# picr22RobodendronMainboard.net
KiCad netlist of a schematic drawn in Altium Designer
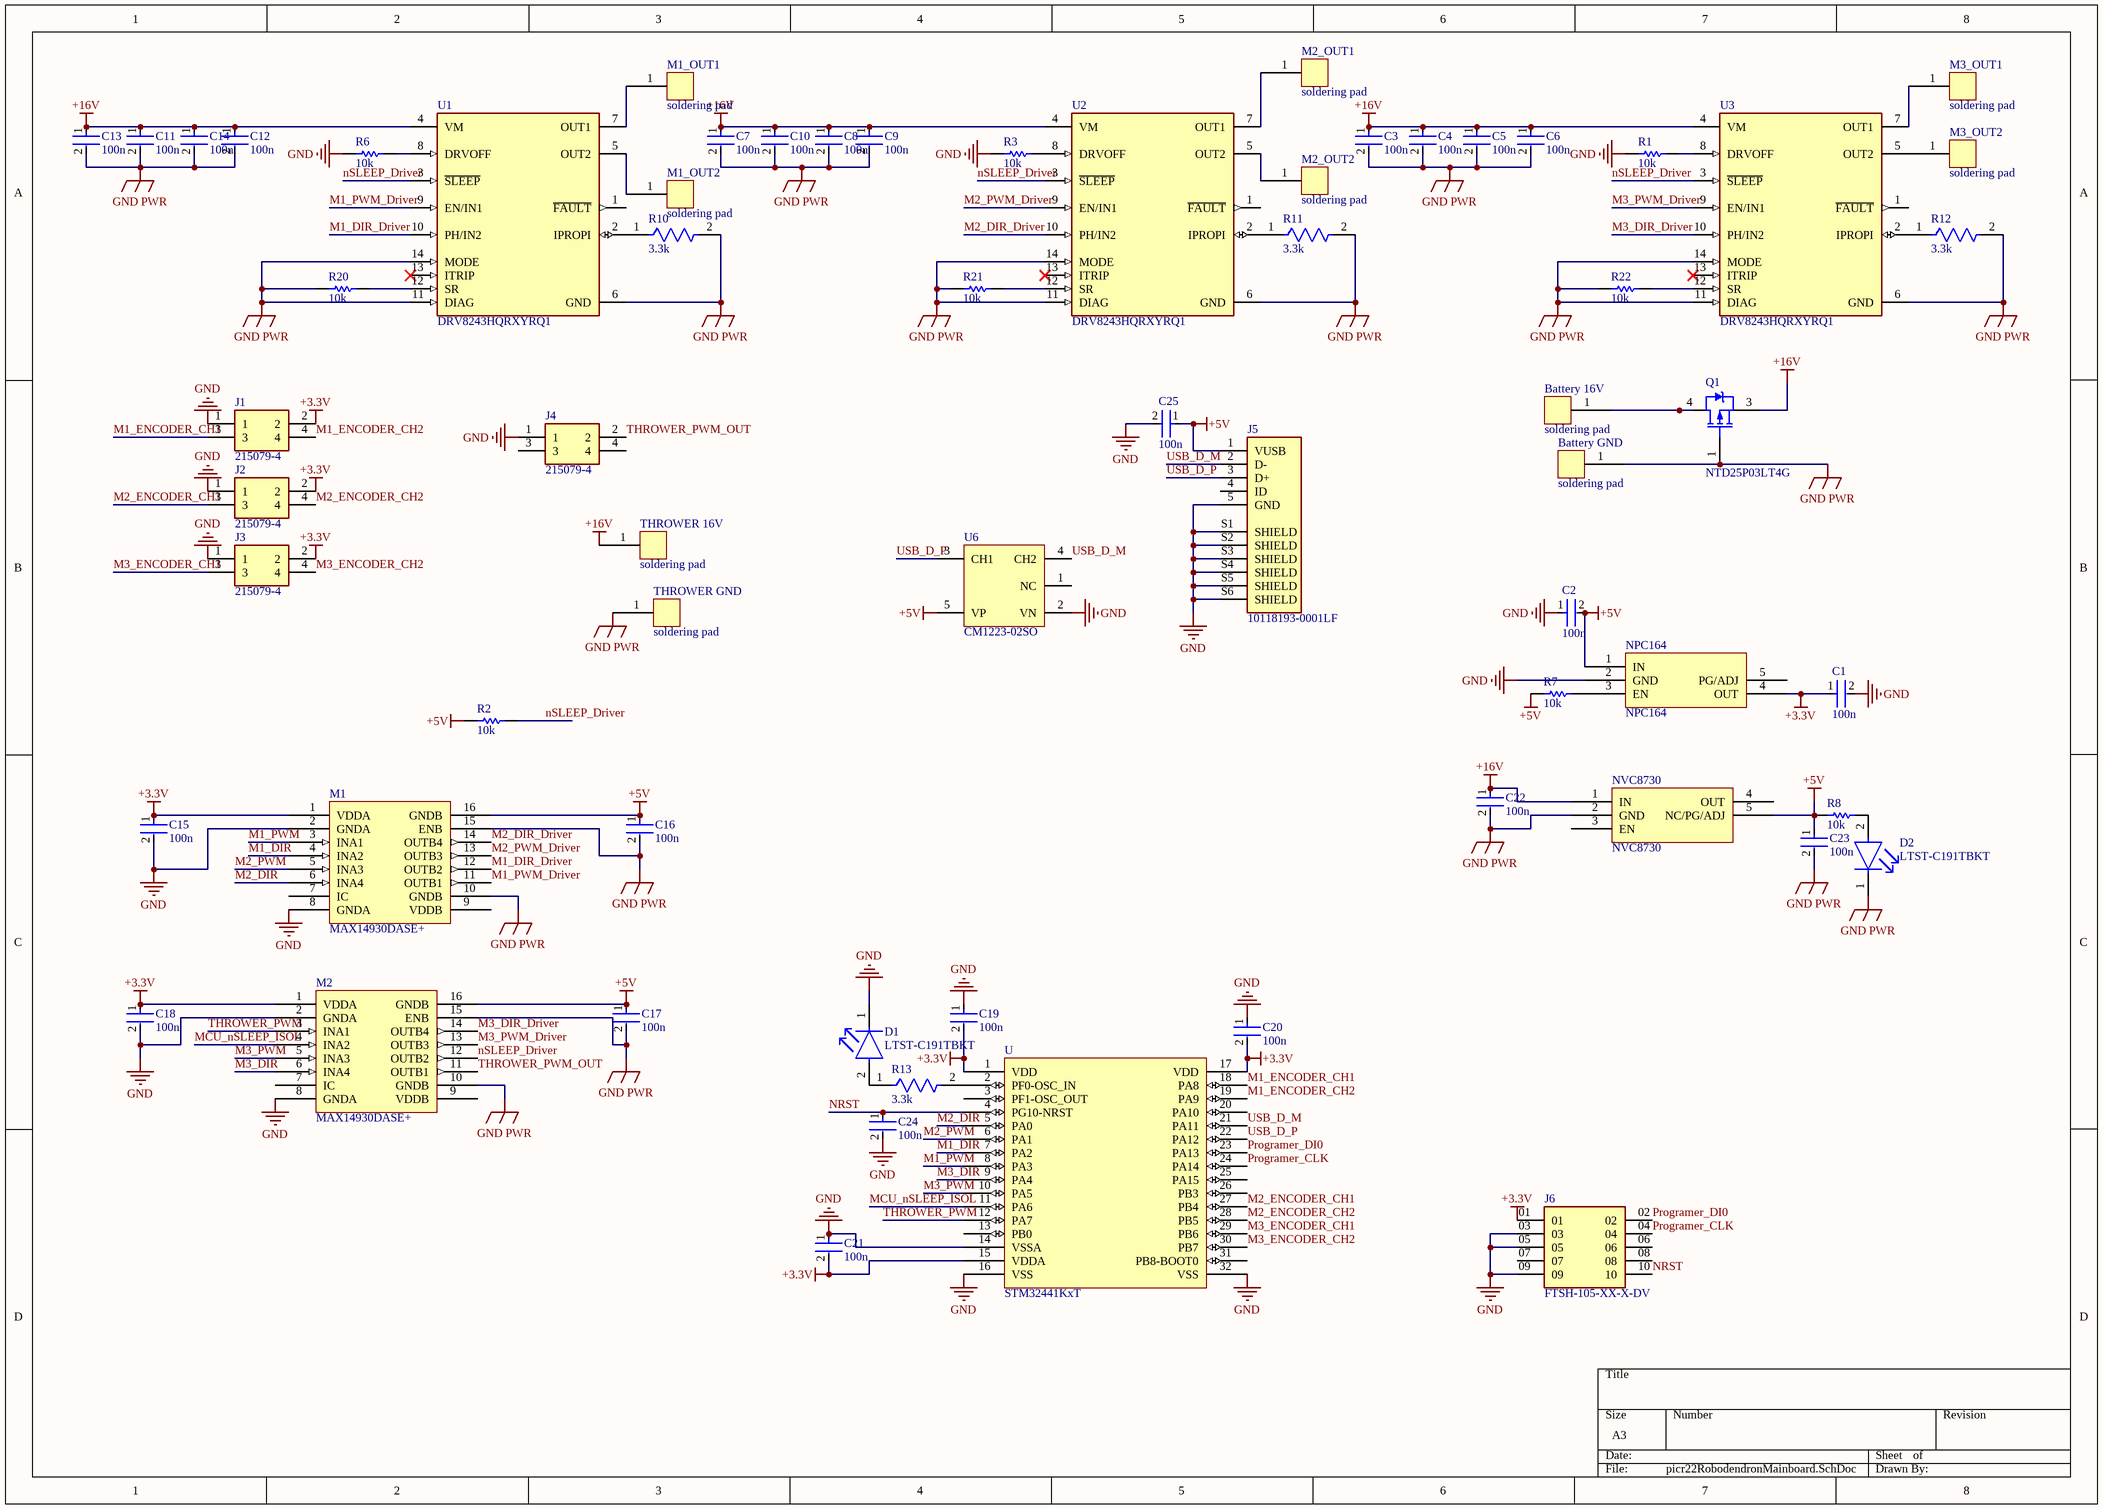
[diagram p0: picr22RobodendronMainboard.SchDoc]

(export (version "E")
  (design (tool "Eeschema 10.0.6"))
  (components
    (comp (ref "Battery 16V")
      (value "soldering pad")
      (footprint "PCBComponent_1")
      (libsource (lib "") (part "soldering pad_1"))
    )
    (comp (ref "Battery GND")
      (value "soldering pad")
      (footprint "PCBComponent_1")
      (libsource (lib "") (part "soldering pad_1"))
    )
    (comp (ref "C1")
      (value "100n")
      (footprint "FP-CGA3E-0_3-0_1-IPC_A")
      (description "Cap Ceramic 100nF 50V X7R 10% Pad SMD 0603 +125°C Automotive T/R")
      (fields (field (name "TOLERANCE") "10%") (field (name "VOLTAGE") "50V"))
      (libsource (lib "Altium Content Vault") (part "b4654b650e69147ec39a6b967a45e02"))
    )
    (comp (ref "C2")
      (value "100n")
      (footprint "FP-CGA3E-0_3-0_1-IPC_A")
      (description "Cap Ceramic 100nF 50V X7R 10% Pad SMD 0603 +125°C Automotive T/R")
      (fields (field (name "TOLERANCE") "10%") (field (name "VOLTAGE") "50V"))
      (libsource (lib "Altium Content Vault") (part "b4654b650e69147ec39a6b967a45e02"))
    )
    (comp (ref "C3")
      (value "100n")
      (footprint "FP-CGA3E-0_3-0_1-IPC_A")
      (description "Cap Ceramic 100nF 50V X7R 10% Pad SMD 0603 +125°C Automotive T/R")
      (fields (field (name "TOLERANCE") "10%") (field (name "VOLTAGE") "50V"))
      (libsource (lib "Altium Content Vault") (part "b4654b650e69147ec39a6b967a45e02"))
    )
    (comp (ref "C4")
      (value "100n")
      (footprint "FP-CGA3E-0_3-0_1-IPC_A")
      (description "Cap Ceramic 100nF 50V X7R 10% Pad SMD 0603 +125°C Automotive T/R")
      (fields (field (name "TOLERANCE") "10%") (field (name "VOLTAGE") "50V"))
      (libsource (lib "Altium Content Vault") (part "b4654b650e69147ec39a6b967a45e02"))
    )
    (comp (ref "C5")
      (value "100n")
      (footprint "FP-CGA3E-0_3-0_1-IPC_A")
      (description "Cap Ceramic 100nF 50V X7R 10% Pad SMD 0603 +125°C Automotive T/R")
      (fields (field (name "TOLERANCE") "10%") (field (name "VOLTAGE") "50V"))
      (libsource (lib "Altium Content Vault") (part "b4654b650e69147ec39a6b967a45e02"))
    )
    (comp (ref "C6")
      (value "100n")
      (footprint "FP-CGA3E-0_3-0_1-IPC_A")
      (description "Cap Ceramic 100nF 50V X7R 10% Pad SMD 0603 +125°C Automotive T/R")
      (fields (field (name "TOLERANCE") "10%") (field (name "VOLTAGE") "50V"))
      (libsource (lib "Altium Content Vault") (part "b4654b650e69147ec39a6b967a45e02"))
    )
    (comp (ref "C7")
      (value "100n")
      (footprint "FP-CGA3E-0_3-0_1-IPC_A")
      (description "Cap Ceramic 100nF 50V X7R 10% Pad SMD 0603 +125°C Automotive T/R")
      (fields (field (name "TOLERANCE") "10%") (field (name "VOLTAGE") "50V"))
      (libsource (lib "Altium Content Vault") (part "b4654b650e69147ec39a6b967a45e02"))
    )
    (comp (ref "C8")
      (value "100n")
      (footprint "FP-CGA3E-0_3-0_1-IPC_A")
      (description "Cap Ceramic 100nF 50V X7R 10% Pad SMD 0603 +125°C Automotive T/R")
      (fields (field (name "TOLERANCE") "10%") (field (name "VOLTAGE") "50V"))
      (libsource (lib "Altium Content Vault") (part "b4654b650e69147ec39a6b967a45e02"))
    )
    (comp (ref "C9")
      (value "100n")
      (footprint "FP-CGA3E-0_3-0_1-IPC_A")
      (description "Cap Ceramic 100nF 50V X7R 10% Pad SMD 0603 +125°C Automotive T/R")
      (fields (field (name "TOLERANCE") "10%") (field (name "VOLTAGE") "50V"))
      (libsource (lib "Altium Content Vault") (part "b4654b650e69147ec39a6b967a45e02"))
    )
    (comp (ref "C10")
      (value "100n")
      (footprint "FP-CGA3E-0_3-0_1-IPC_A")
      (description "Cap Ceramic 100nF 50V X7R 10% Pad SMD 0603 +125°C Automotive T/R")
      (fields (field (name "TOLERANCE") "10%") (field (name "VOLTAGE") "50V"))
      (libsource (lib "Altium Content Vault") (part "b4654b650e69147ec39a6b967a45e02"))
    )
    (comp (ref "C11")
      (value "100n")
      (footprint "FP-CGA3E-0_3-0_1-IPC_A")
      (description "Cap Ceramic 100nF 50V X7R 10% Pad SMD 0603 +125°C Automotive T/R")
      (fields (field (name "TOLERANCE") "10%") (field (name "VOLTAGE") "50V"))
      (libsource (lib "Altium Content Vault") (part "b4654b650e69147ec39a6b967a45e02"))
    )
    (comp (ref "C12")
      (value "100n")
      (footprint "FP-CGA3E-0_3-0_1-IPC_A")
      (description "Cap Ceramic 100nF 50V X7R 10% Pad SMD 0603 +125°C Automotive T/R")
      (fields (field (name "TOLERANCE") "10%") (field (name "VOLTAGE") "50V"))
      (libsource (lib "Altium Content Vault") (part "b4654b650e69147ec39a6b967a45e02"))
    )
    (comp (ref "C13")
      (value "100n")
      (footprint "FP-CGA3E-0_3-0_1-IPC_A")
      (description "Cap Ceramic 100nF 50V X7R 10% Pad SMD 0603 +125°C Automotive T/R")
      (fields (field (name "TOLERANCE") "10%") (field (name "VOLTAGE") "50V"))
      (libsource (lib "Altium Content Vault") (part "b4654b650e69147ec39a6b967a45e02"))
    )
    (comp (ref "C14")
      (value "100n")
      (footprint "FP-CGA3E-0_3-0_1-IPC_A")
      (description "Cap Ceramic 100nF 50V X7R 10% Pad SMD 0603 +125°C Automotive T/R")
      (fields (field (name "TOLERANCE") "10%") (field (name "VOLTAGE") "50V"))
      (libsource (lib "Altium Content Vault") (part "b4654b650e69147ec39a6b967a45e02"))
    )
    (comp (ref "C15")
      (value "100n")
      (footprint "FP-CGA3E-0_3-0_1-IPC_A")
      (description "Cap Ceramic 100nF 50V X7R 10% Pad SMD 0603 +125°C Automotive T/R")
      (fields (field (name "TOLERANCE") "10%") (field (name "VOLTAGE") "50V"))
      (libsource (lib "Altium Content Vault") (part "b4654b650e69147ec39a6b967a45e02"))
    )
    (comp (ref "C16")
      (value "100n")
      (footprint "FP-CGA3E-0_3-0_1-IPC_A")
      (description "Cap Ceramic 100nF 50V X7R 10% Pad SMD 0603 +125°C Automotive T/R")
      (fields (field (name "TOLERANCE") "10%") (field (name "VOLTAGE") "50V"))
      (libsource (lib "Altium Content Vault") (part "b4654b650e69147ec39a6b967a45e02"))
    )
    (comp (ref "C17")
      (value "100n")
      (footprint "FP-CGA3E-0_3-0_1-IPC_A")
      (description "Cap Ceramic 100nF 50V X7R 10% Pad SMD 0603 +125°C Automotive T/R")
      (fields (field (name "TOLERANCE") "10%") (field (name "VOLTAGE") "50V"))
      (libsource (lib "Altium Content Vault") (part "b4654b650e69147ec39a6b967a45e02"))
    )
    (comp (ref "C18")
      (value "100n")
      (footprint "FP-CGA3E-0_3-0_1-IPC_A")
      (description "Cap Ceramic 100nF 50V X7R 10% Pad SMD 0603 +125°C Automotive T/R")
      (fields (field (name "TOLERANCE") "10%") (field (name "VOLTAGE") "50V"))
      (libsource (lib "Altium Content Vault") (part "b4654b650e69147ec39a6b967a45e02"))
    )
    (comp (ref "C19")
      (value "100n")
      (footprint "FP-CGA3E-0_3-0_1-IPC_A")
      (description "Cap Ceramic 100nF 50V X7R 10% Pad SMD 0603 +125°C Automotive T/R")
      (fields (field (name "TOLERANCE") "10%") (field (name "VOLTAGE") "50V"))
      (libsource (lib "Altium Content Vault") (part "b4654b650e69147ec39a6b967a45e02"))
    )
    (comp (ref "C20")
      (value "100n")
      (footprint "FP-CGA3E-0_3-0_1-IPC_A")
      (description "Cap Ceramic 100nF 50V X7R 10% Pad SMD 0603 +125°C Automotive T/R")
      (fields (field (name "TOLERANCE") "10%") (field (name "VOLTAGE") "50V"))
      (libsource (lib "Altium Content Vault") (part "b4654b650e69147ec39a6b967a45e02"))
    )
    (comp (ref "C21")
      (value "100n")
      (footprint "FP-CGA3E-0_3-0_1-IPC_A")
      (description "Cap Ceramic 100nF 50V X7R 10% Pad SMD 0603 +125°C Automotive T/R")
      (fields (field (name "TOLERANCE") "10%") (field (name "VOLTAGE") "50V"))
      (libsource (lib "Altium Content Vault") (part "b4654b650e69147ec39a6b967a45e02"))
    )
    (comp (ref "C22")
      (value "100n")
      (footprint "FP-CGA3E-0_3-0_1-IPC_A")
      (description "Cap Ceramic 100nF 50V X7R 10% Pad SMD 0603 +125°C Automotive T/R")
      (fields (field (name "TOLERANCE") "10%") (field (name "VOLTAGE") "50V"))
      (libsource (lib "Altium Content Vault") (part "b4654b650e69147ec39a6b967a45e02"))
    )
    (comp (ref "C23")
      (value "100n")
      (footprint "FP-CGA3E-0_3-0_1-IPC_A")
      (description "Cap Ceramic 100nF 50V X7R 10% Pad SMD 0603 +125°C Automotive T/R")
      (fields (field (name "TOLERANCE") "10%") (field (name "VOLTAGE") "50V"))
      (libsource (lib "Altium Content Vault") (part "b4654b650e69147ec39a6b967a45e02"))
    )
    (comp (ref "C24")
      (value "100n")
      (footprint "FP-CGA3E-0_3-0_1-IPC_A")
      (description "Cap Ceramic 100nF 50V X7R 10% Pad SMD 0603 +125°C Automotive T/R")
      (fields (field (name "TOLERANCE") "10%") (field (name "VOLTAGE") "50V"))
      (libsource (lib "Altium Content Vault") (part "b4654b650e69147ec39a6b967a45e02"))
    )
    (comp (ref "C25")
      (value "100n")
      (footprint "FP-CGA3E-0_3-0_1-IPC_A")
      (description "Cap Ceramic 100nF 50V X7R 10% Pad SMD 0603 +125°C Automotive T/R")
      (fields (field (name "TOLERANCE") "10%") (field (name "VOLTAGE") "50V"))
      (libsource (lib "Altium Content Vault") (part "b4654b650e69147ec39a6b967a45e02"))
    )
    (comp (ref "D1")
      (value "LTST-C191TBKT")
      (footprint "FP-LTST-C191TBKT-MFG")
      (description "LED BLUE CLEAR CHIP SMD")
      (libsource (lib "Altium Content Vault") (part "8706943c75ba83719d021d2fdc84c58"))
    )
    (comp (ref "D2")
      (value "LTST-C191TBKT")
      (footprint "FP-LTST-C191TBKT-MFG")
      (description "LED BLUE CLEAR CHIP SMD")
      (libsource (lib "Altium Content Vault") (part "8706943c75ba83719d021d2fdc84c58"))
    )
    (comp (ref "J1")
      (value "215079-4")
      (footprint "TE_215079-4")
      (description "4 Position Receptacle Connector Through Hole")
      (fields (field (name "MF") "TE Connectivity"))
      (libsource (lib "215079-4") (part "215079-4"))
    )
    (comp (ref "J2")
      (value "215079-4")
      (footprint "TE_215079-4")
      (description "4 Position Receptacle Connector Through Hole")
      (fields (field (name "MF") "TE Connectivity"))
      (libsource (lib "215079-4") (part "215079-4"))
    )
    (comp (ref "J3")
      (value "215079-4")
      (footprint "TE_215079-4")
      (description "4 Position Receptacle Connector Through Hole")
      (fields (field (name "MF") "TE Connectivity"))
      (libsource (lib "215079-4") (part "215079-4"))
    )
    (comp (ref "J4")
      (value "215079-4")
      (footprint "TE_215079-4")
      (description "4 Position Receptacle Connector Through Hole")
      (fields (field (name "MF") "TE Connectivity"))
      (libsource (lib "215079-4") (part "215079-4"))
    )
    (comp (ref "J5")
      (value "10118193-0001LF")
      (footprint "FCI_10118193-0001LF")
      (description "USB - micro B USB 2.0 Receptacle Connector 5 Position Surface Mount, Right Angle; Through Hole")
      (fields (field (name "MF") "Amphenol ICC"))
      (libsource (lib "10118193-0001LF") (part "10118193-0001LF"))
    )
    (comp (ref "J6")
      (value "FTSH-105-XX-X-DV")
      (footprint "SAMTEC_FTSH-105-XX-X-DV")
      (description "Connector Header Surface Mount 10 position 0.050\" (1.27mm)")
      (libsource (lib "FTSH-105-XX-X-DV") (part "FTSH-105-XX-X-DV"))
    )
    (comp (ref "M1")
      (value "MAX14930DASE+")
      (footprint "SOIC127P600X175-16N")
      (libsource (lib "picr22RobodendronMainboard") (part "MAX14930DASE+"))
    )
    (comp (ref "M1_OUT1")
      (value "soldering pad")
      (footprint "PCBComponent_1")
      (libsource (lib "picr22RobodendronMainboard") (part "soldering pad"))
    )
    (comp (ref "M1_OUT2")
      (value "soldering pad")
      (footprint "PCBComponent_1")
      (libsource (lib "picr22RobodendronMainboard") (part "soldering pad"))
    )
    (comp (ref "M2")
      (value "MAX14930DASE+")
      (footprint "SOIC127P600X175-16N")
      (libsource (lib "picr22RobodendronMainboard") (part "MAX14930DASE+"))
    )
    (comp (ref "M2_OUT1")
      (value "soldering pad")
      (footprint "PCBComponent_1")
      (libsource (lib "picr22RobodendronMainboard") (part "soldering pad"))
    )
    (comp (ref "M2_OUT2")
      (value "soldering pad")
      (footprint "PCBComponent_1")
      (libsource (lib "picr22RobodendronMainboard") (part "soldering pad"))
    )
    (comp (ref "M3_OUT1")
      (value "soldering pad")
      (footprint "PCBComponent_1")
      (libsource (lib "picr22RobodendronMainboard") (part "soldering pad"))
    )
    (comp (ref "M3_OUT2")
      (value "soldering pad")
      (footprint "PCBComponent_1")
      (libsource (lib "picr22RobodendronMainboard") (part "soldering pad"))
    )
    (comp (ref "NPC164")
      (value "NPC164")
      (footprint "TSOP95P280X110-5N")
      (libsource (lib "picr22RobodendronMainboard") (part "NPC164"))
    )
    (comp (ref "NVC8730")
      (value "NVC8730")
      (footprint "TSOP95P280X110-6N")
      (libsource (lib "picr22RobodendronMainboard") (part "NVC8730"))
    )
    (comp (ref "Q1")
      (value "NTD25P03LT4G")
      (footprint "ONSC-DPAK-3-369C-01_V")
      (description "Power MOSFET, -25 A, -30 V, Logic Level P-Channel, 3-Pin DPAK, Pb-Free, Tape and Reel")
      (fields (field (name "MANUFACTURER") "On Semiconductor"))
      (libsource (lib "Altium Content Vault") (part "ONSC-PMOS-G1S3D4-3_B"))
    )
    (comp (ref "R1")
      (value "10k")
      (footprint "RESC1609X50X30NL8T20")
      (description "Chip Resistor, 10 KOhm, +/- 1%, 100 mW, -55 to 155 degC, 0603 (1608 Metric), RoHS, Tape and Reel")
      (fields (field (name "MANUFACTURER") "Vishay Semiconductor"))
      (libsource (lib "Altium Content Vault") (part "RES-2"))
    )
    (comp (ref "R2")
      (value "10k")
      (footprint "RESC1609X50X30NL8T20")
      (description "Chip Resistor, 10 KOhm, +/- 1%, 100 mW, -55 to 155 degC, 0603 (1608 Metric), RoHS, Tape and Reel")
      (fields (field (name "MANUFACTURER") "Vishay Semiconductor"))
      (libsource (lib "Altium Content Vault") (part "RES-2"))
    )
    (comp (ref "R3")
      (value "10k")
      (footprint "RESC1609X50X30NL8T20")
      (description "Chip Resistor, 10 KOhm, +/- 1%, 100 mW, -55 to 155 degC, 0603 (1608 Metric), RoHS, Tape and Reel")
      (fields (field (name "MANUFACTURER") "Vishay Semiconductor"))
      (libsource (lib "Altium Content Vault") (part "RES-2"))
    )
    (comp (ref "R6")
      (value "10k")
      (footprint "RESC1609X50X30NL8T20")
      (description "Chip Resistor, 10 KOhm, +/- 1%, 100 mW, -55 to 155 degC, 0603 (1608 Metric), RoHS, Tape and Reel")
      (fields (field (name "MANUFACTURER") "Vishay Semiconductor"))
      (libsource (lib "Altium Content Vault") (part "RES-2"))
    )
    (comp (ref "R7")
      (value "10k")
      (footprint "RESC1609X50X30NL8T20")
      (description "Chip Resistor, 10 KOhm, +/- 1%, 100 mW, -55 to 155 degC, 0603 (1608 Metric), RoHS, Tape and Reel")
      (fields (field (name "MANUFACTURER") "Vishay Semiconductor"))
      (libsource (lib "Altium Content Vault") (part "RES-2"))
    )
    (comp (ref "R8")
      (value "10k")
      (footprint "RESC1609X50X30NL8T20")
      (description "Chip Resistor, 10 KOhm, +/- 1%, 100 mW, -55 to 155 degC, 0603 (1608 Metric), RoHS, Tape and Reel")
      (fields (field (name "MANUFACTURER") "Vishay Semiconductor"))
      (libsource (lib "Altium Content Vault") (part "RES-2"))
    )
    (comp (ref "R10")
      (value "3.3k")
      (footprint "FP-ERA3A-IPC_B")
      (description "RES SMD 3.3K OHM 0.1% 1/10W 0603")
      (fields (field (name "TOLERANCE") "0.1%"))
      (libsource (lib "Altium Content Vault") (part "1029c3af85768c4190bb7ad29bc67b5"))
    )
    (comp (ref "R11")
      (value "3.3k")
      (footprint "FP-ERA3A-IPC_B")
      (description "RES SMD 3.3K OHM 0.1% 1/10W 0603")
      (fields (field (name "TOLERANCE") "0.1%"))
      (libsource (lib "Altium Content Vault") (part "1029c3af85768c4190bb7ad29bc67b5"))
    )
    (comp (ref "R12")
      (value "3.3k")
      (footprint "FP-ERA3A-IPC_B")
      (description "RES SMD 3.3K OHM 0.1% 1/10W 0603")
      (fields (field (name "TOLERANCE") "0.1%"))
      (libsource (lib "Altium Content Vault") (part "1029c3af85768c4190bb7ad29bc67b5"))
    )
    (comp (ref "R13")
      (value "3.3k")
      (footprint "FP-ERA3A-IPC_B")
      (description "RES SMD 3.3K OHM 0.1% 1/10W 0603")
      (fields (field (name "TOLERANCE") "0.1%"))
      (libsource (lib "Altium Content Vault") (part "1029c3af85768c4190bb7ad29bc67b5"))
    )
    (comp (ref "R20")
      (value "10k")
      (footprint "RESC1609X50X30NL8T20")
      (description "Chip Resistor, 10 KOhm, +/- 1%, 100 mW, -55 to 155 degC, 0603 (1608 Metric), RoHS, Tape and Reel")
      (fields (field (name "MANUFACTURER") "Vishay Semiconductor"))
      (libsource (lib "Altium Content Vault") (part "RES-2"))
    )
    (comp (ref "R21")
      (value "10k")
      (footprint "RESC1609X50X30NL8T20")
      (description "Chip Resistor, 10 KOhm, +/- 1%, 100 mW, -55 to 155 degC, 0603 (1608 Metric), RoHS, Tape and Reel")
      (fields (field (name "MANUFACTURER") "Vishay Semiconductor"))
      (libsource (lib "Altium Content Vault") (part "RES-2"))
    )
    (comp (ref "R22")
      (value "10k")
      (footprint "RESC1609X50X30NL8T20")
      (description "Chip Resistor, 10 KOhm, +/- 1%, 100 mW, -55 to 155 degC, 0603 (1608 Metric), RoHS, Tape and Reel")
      (fields (field (name "MANUFACTURER") "Vishay Semiconductor"))
      (libsource (lib "Altium Content Vault") (part "RES-2"))
    )
    (comp (ref "THROWER 16V")
      (value "soldering pad")
      (footprint "PCBComponent_1")
      (libsource (lib "picr22RobodendronMainboard") (part "soldering pad"))
    )
    (comp (ref "THROWER GND")
      (value "soldering pad")
      (footprint "PCBComponent_1")
      (libsource (lib "picr22RobodendronMainboard") (part "soldering pad"))
    )
    (comp (ref "U")
      (value "STM32441KxT")
      (footprint "TQFP80P890X890X160-32N")
      (libsource (lib "picr22RobodendronMainboard") (part "STM32441"))
    )
    (comp (ref "U1")
      (value "DRV8243HQRXYRQ1")
      (footprint "FP-RXY0014A-MFG")
      (libsource (lib "Altium Content Vault") (part "e63e13eb07ecfdbca845f52d5221c39"))
    )
    (comp (ref "U2")
      (value "DRV8243HQRXYRQ1")
      (footprint "FP-RXY0014A-MFG")
      (libsource (lib "Altium Content Vault") (part "e63e13eb07ecfdbca845f52d5221c39"))
    )
    (comp (ref "U3")
      (value "DRV8243HQRXYRQ1")
      (footprint "FP-RXY0014A-MFG")
      (libsource (lib "Altium Content Vault") (part "e63e13eb07ecfdbca845f52d5221c39"))
    )
    (comp (ref "U6")
      (value "CM1223-02SO")
      (footprint "ONSC-SOT23-5-527AH-01_L")
      (fields (field (name "MANUFACTURER") "On Semiconductor"))
      (libsource (lib "Altium Content Vault") (part "ONSC-CM1223-SOT-23-5-527AH-01"))
    )
  )
  (nets
    (net (code "1") (name "+3.3V") (class "Default")
      (node (ref "C1") (pin "1") (pinfunction "1_1") (pintype "passive"))
      (node (ref "C15") (pin "1") (pinfunction "1_1") (pintype "passive"))
      (node (ref "C18") (pin "1") (pinfunction "1_1") (pintype "passive"))
      (node (ref "C19") (pin "2") (pinfunction "2_2") (pintype "passive"))
      (node (ref "C20") (pin "2") (pinfunction "2_2") (pintype "passive"))
      (node (ref "C21") (pin "2") (pinfunction "2_2") (pintype "passive"))
      (node (ref "J1") (pin "2") (pinfunction "2_2") (pintype "passive"))
      (node (ref "J2") (pin "2") (pinfunction "2_2") (pintype "passive"))
      (node (ref "J3") (pin "2") (pinfunction "2_2") (pintype "passive"))
      (node (ref "J6") (pin "01") (pinfunction "01_01") (pintype "passive"))
      (node (ref "M1") (pin "1") (pinfunction "VDDA_1") (pintype "power_in"))
      (node (ref "M2") (pin "1") (pinfunction "VDDA_1") (pintype "power_in"))
      (node (ref "NPC164") (pin "4") (pinfunction "OUT_4") (pintype "power_in"))
      (node (ref "U") (pin "1") (pinfunction "VDD_1") (pintype "power_in"))
      (node (ref "U") (pin "15") (pinfunction "VDDA_15") (pintype "power_in"))
      (node (ref "U") (pin "17") (pinfunction "VDD_17") (pintype "power_in"))
    )
    (net (code "2") (name "+5V") (class "Default")
      (node (ref "C16") (pin "1") (pinfunction "1_1") (pintype "passive"))
      (node (ref "C17") (pin "1") (pinfunction "1_1") (pintype "passive"))
      (node (ref "C2") (pin "2") (pinfunction "2_2") (pintype "passive"))
      (node (ref "C23") (pin "1") (pinfunction "1_1") (pintype "passive"))
      (node (ref "C25") (pin "1") (pinfunction "1_1") (pintype "passive"))
      (node (ref "J5") (pin "1") (pinfunction "VUSB_1") (pintype "passive"))
      (node (ref "M1") (pin "16") (pinfunction "GNDB_16") (pintype "power_in"))
      (node (ref "M2") (pin "16") (pinfunction "GNDB_16") (pintype "power_in"))
      (node (ref "NPC164") (pin "1") (pinfunction "IN_1") (pintype "power_in"))
      (node (ref "NVC8730") (pin "5") (pinfunction "NC/PG/ADJ_5") (pintype "passive"))
      (node (ref "R2") (pin "1") (pinfunction "1_1") (pintype "passive"))
      (node (ref "R7") (pin "1") (pinfunction "1_1") (pintype "passive"))
      (node (ref "R8") (pin "1") (pinfunction "1_1") (pintype "passive"))
      (node (ref "U6") (pin "5") (pinfunction "VP_5") (pintype "power_in"))
    )
    (net (code "3") (name "+16V") (class "Default")
      (node (ref "C10") (pin "1") (pinfunction "1_1") (pintype "passive"))
      (node (ref "C11") (pin "1") (pinfunction "1_1") (pintype "passive"))
      (node (ref "C12") (pin "1") (pinfunction "1_1") (pintype "passive"))
      (node (ref "C13") (pin "1") (pinfunction "1_1") (pintype "passive"))
      (node (ref "C14") (pin "1") (pinfunction "1_1") (pintype "passive"))
      (node (ref "C22") (pin "1") (pinfunction "1_1") (pintype "passive"))
      (node (ref "C3") (pin "1") (pinfunction "1_1") (pintype "passive"))
      (node (ref "C4") (pin "1") (pinfunction "1_1") (pintype "passive"))
      (node (ref "C5") (pin "1") (pinfunction "1_1") (pintype "passive"))
      (node (ref "C6") (pin "1") (pinfunction "1_1") (pintype "passive"))
      (node (ref "C7") (pin "1") (pinfunction "1_1") (pintype "passive"))
      (node (ref "C8") (pin "1") (pinfunction "1_1") (pintype "passive"))
      (node (ref "C9") (pin "1") (pinfunction "1_1") (pintype "passive"))
      (node (ref "NVC8730") (pin "1") (pinfunction "IN_1") (pintype "power_in"))
      (node (ref "Q1") (pin "3") (pinfunction "S_3") (pintype "passive"))
      (node (ref "THROWER 16V") (pin "1") (pintype "power_in"))
      (node (ref "U1") (pin "4") (pinfunction "VM_4") (pintype "power_in"))
      (node (ref "U2") (pin "4") (pinfunction "VM_4") (pintype "power_in"))
      (node (ref "U3") (pin "4") (pinfunction "VM_4") (pintype "power_in"))
    )
    (net (code "4") (name "/M1_DIR") (class "Default")
      (node (ref "M1") (pin "4") (pinfunction "INA2_4") (pintype "input"))
      (node (ref "U") (pin "7") (pinfunction "PA2_7") (pintype "bidirectional"))
    )
    (net (code "5") (name "/M1_DIR_Driver") (class "Default")
      (node (ref "M1") (pin "12") (pinfunction "OUTB2_12") (pintype "output"))
      (node (ref "U1") (pin "10") (pinfunction "PH/IN2_10") (pintype "input"))
    )
    (net (code "6") (name "/M1_ENCODER_CH1") (class "Default")
      (node (ref "J1") (pin "3") (pinfunction "3_3") (pintype "passive"))
      (node (ref "U") (pin "18") (pinfunction "PA8_18") (pintype "bidirectional"))
    )
    (net (code "7") (name "/M1_ENCODER_CH2") (class "Default")
      (node (ref "J1") (pin "4") (pinfunction "4_4") (pintype "passive"))
      (node (ref "U") (pin "19") (pinfunction "PA9_19") (pintype "bidirectional"))
    )
    (net (code "8") (name "/M1_PWM") (class "Default")
      (node (ref "M1") (pin "3") (pinfunction "INA1_3") (pintype "input"))
      (node (ref "U") (pin "8") (pinfunction "PA3_8") (pintype "bidirectional"))
    )
    (net (code "9") (name "/M1_PWM_Driver") (class "Default")
      (node (ref "M1") (pin "11") (pinfunction "OUTB1_11") (pintype "output"))
      (node (ref "U1") (pin "9") (pinfunction "EN/IN1_9") (pintype "input"))
    )
    (net (code "10") (name "/M2_DIR") (class "Default")
      (node (ref "M1") (pin "6") (pinfunction "INA4_6") (pintype "input"))
      (node (ref "U") (pin "5") (pinfunction "PA0_5") (pintype "bidirectional"))
    )
    (net (code "11") (name "/M2_DIR_Driver") (class "Default")
      (node (ref "M1") (pin "14") (pinfunction "OUTB4_14") (pintype "output"))
      (node (ref "U2") (pin "10") (pinfunction "PH/IN2_10") (pintype "input"))
    )
    (net (code "12") (name "/M2_ENCODER_CH1") (class "Default")
      (node (ref "J2") (pin "3") (pinfunction "3_3") (pintype "passive"))
      (node (ref "U") (pin "27") (pinfunction "PB4_27") (pintype "bidirectional"))
    )
    (net (code "13") (name "/M2_ENCODER_CH2") (class "Default")
      (node (ref "J2") (pin "4") (pinfunction "4_4") (pintype "passive"))
      (node (ref "U") (pin "28") (pinfunction "PB5_28") (pintype "bidirectional"))
    )
    (net (code "14") (name "/M2_PWM") (class "Default")
      (node (ref "M1") (pin "5") (pinfunction "INA3_5") (pintype "input"))
      (node (ref "U") (pin "6") (pinfunction "PA1_6") (pintype "bidirectional"))
    )
    (net (code "15") (name "/M2_PWM_Driver") (class "Default")
      (node (ref "M1") (pin "13") (pinfunction "OUTB3_13") (pintype "output"))
      (node (ref "U2") (pin "9") (pinfunction "EN/IN1_9") (pintype "input"))
    )
    (net (code "16") (name "/M3_DIR") (class "Default")
      (node (ref "M2") (pin "6") (pinfunction "INA4_6") (pintype "input"))
      (node (ref "U") (pin "9") (pinfunction "PA4_9") (pintype "bidirectional"))
    )
    (net (code "17") (name "/M3_DIR_Driver") (class "Default")
      (node (ref "M2") (pin "14") (pinfunction "OUTB4_14") (pintype "output"))
      (node (ref "U3") (pin "10") (pinfunction "PH/IN2_10") (pintype "input"))
    )
    (net (code "18") (name "/M3_ENCODER_CH1") (class "Default")
      (node (ref "J3") (pin "3") (pinfunction "3_3") (pintype "passive"))
      (node (ref "U") (pin "29") (pinfunction "PB6_29") (pintype "bidirectional"))
    )
    (net (code "19") (name "/M3_ENCODER_CH2") (class "Default")
      (node (ref "J3") (pin "4") (pinfunction "4_4") (pintype "passive"))
      (node (ref "U") (pin "30") (pinfunction "PB7_30") (pintype "bidirectional"))
    )
    (net (code "20") (name "/M3_PWM") (class "Default")
      (node (ref "M2") (pin "5") (pinfunction "INA3_5") (pintype "input"))
      (node (ref "U") (pin "10") (pinfunction "PA5_10") (pintype "bidirectional"))
    )
    (net (code "21") (name "/M3_PWM_Driver") (class "Default")
      (node (ref "M2") (pin "13") (pinfunction "OUTB3_13") (pintype "output"))
      (node (ref "U3") (pin "9") (pinfunction "EN/IN1_9") (pintype "input"))
    )
    (net (code "22") (name "/MCU_nSLEEP_ISOL") (class "Default")
      (node (ref "M2") (pin "4") (pinfunction "INA2_4") (pintype "input"))
      (node (ref "U") (pin "11") (pinfunction "PA6_11") (pintype "bidirectional"))
    )
    (net (code "23") (name "/NRST") (class "Default")
      (node (ref "C24") (pin "1") (pinfunction "1_1") (pintype "passive"))
      (node (ref "J6") (pin "10") (pinfunction "10_10") (pintype "passive"))
      (node (ref "U") (pin "4") (pinfunction "PG10-NRST_4") (pintype "bidirectional"))
    )
    (net (code "24") (name "/Programer_CLK") (class "Default")
      (node (ref "J6") (pin "04") (pinfunction "04_04") (pintype "passive"))
      (node (ref "U") (pin "24") (pinfunction "PA14_24") (pintype "bidirectional"))
    )
    (net (code "25") (name "/Programer_DI0") (class "Default")
      (node (ref "J6") (pin "02") (pinfunction "02_02") (pintype "passive"))
      (node (ref "U") (pin "23") (pinfunction "PA13_23") (pintype "bidirectional"))
    )
    (net (code "26") (name "/THROWER_PWM") (class "Default")
      (node (ref "M2") (pin "3") (pinfunction "INA1_3") (pintype "input"))
      (node (ref "U") (pin "12") (pinfunction "PA7_12") (pintype "bidirectional"))
    )
    (net (code "27") (name "/THROWER_PWM_OUT") (class "Default")
      (node (ref "J4") (pin "2") (pinfunction "2_2") (pintype "passive"))
      (node (ref "M2") (pin "11") (pinfunction "OUTB1_11") (pintype "output"))
    )
    (net (code "28") (name "/USB_D_M") (class "Default")
      (node (ref "J5") (pin "2") (pinfunction "D-_2") (pintype "passive"))
      (node (ref "U") (pin "21") (pinfunction "PA11_21") (pintype "bidirectional"))
      (node (ref "U6") (pin "4") (pinfunction "CH2_4") (pintype "passive"))
    )
    (net (code "29") (name "/USB_D_P") (class "Default")
      (node (ref "J5") (pin "3") (pinfunction "D+_3") (pintype "passive"))
      (node (ref "U") (pin "22") (pinfunction "PA12_22") (pintype "bidirectional"))
      (node (ref "U6") (pin "3") (pinfunction "CH1_3") (pintype "passive"))
    )
    (net (code "30") (name "/nSLEEP_Driver") (class "Default")
      (node (ref "M2") (pin "12") (pinfunction "OUTB2_12") (pintype "output"))
      (node (ref "R2") (pin "2") (pinfunction "2_2") (pintype "passive"))
      (node (ref "U1") (pin "3") (pinfunction "~{SLEEP}_3") (pintype "input"))
      (node (ref "U2") (pin "3") (pinfunction "~{SLEEP}_3") (pintype "input"))
      (node (ref "U3") (pin "3") (pinfunction "~{SLEEP}_3") (pintype "input"))
    )
    (net (code "31") (name "GND") (class "Default")
      (node (ref "C1") (pin "2") (pinfunction "2_2") (pintype "passive"))
      (node (ref "C15") (pin "2") (pinfunction "2_2") (pintype "passive"))
      (node (ref "C18") (pin "2") (pinfunction "2_2") (pintype "passive"))
      (node (ref "C19") (pin "1") (pinfunction "1_1") (pintype "passive"))
      (node (ref "C2") (pin "1") (pinfunction "1_1") (pintype "passive"))
      (node (ref "C20") (pin "1") (pinfunction "1_1") (pintype "passive"))
      (node (ref "C21") (pin "1") (pinfunction "1_1") (pintype "passive"))
      (node (ref "C24") (pin "2") (pinfunction "2_2") (pintype "passive"))
      (node (ref "C25") (pin "2") (pinfunction "2_2") (pintype "passive"))
      (node (ref "D1") (pin "1") (pinfunction "C_1") (pintype "passive"))
      (node (ref "J1") (pin "1") (pinfunction "1_1") (pintype "passive"))
      (node (ref "J2") (pin "1") (pinfunction "1_1") (pintype "passive"))
      (node (ref "J3") (pin "1") (pinfunction "1_1") (pintype "passive"))
      (node (ref "J4") (pin "1") (pinfunction "1_1") (pintype "passive"))
      (node (ref "J5") (pin "5") (pinfunction "GND_5") (pintype "passive"))
      (node (ref "J5") (pin "S1") (pinfunction "SHIELD_S1") (pintype "passive"))
      (node (ref "J5") (pin "S2") (pinfunction "SHIELD_S2") (pintype "passive"))
      (node (ref "J5") (pin "S3") (pinfunction "SHIELD_S3") (pintype "passive"))
      (node (ref "J5") (pin "S4") (pinfunction "SHIELD_S4") (pintype "passive"))
      (node (ref "J5") (pin "S5") (pinfunction "SHIELD_S5") (pintype "passive"))
      (node (ref "J5") (pin "S6") (pinfunction "SHIELD_S6") (pintype "passive"))
      (node (ref "J6") (pin "03") (pinfunction "03_03") (pintype "passive"))
      (node (ref "J6") (pin "05") (pinfunction "05_05") (pintype "passive"))
      (node (ref "J6") (pin "09") (pinfunction "09_09") (pintype "passive"))
      (node (ref "M1") (pin "2") (pinfunction "GNDA_2") (pintype "power_in"))
      (node (ref "M1") (pin "8") (pinfunction "GNDA_8") (pintype "power_in"))
      (node (ref "M2") (pin "2") (pinfunction "GNDA_2") (pintype "power_in"))
      (node (ref "M2") (pin "8") (pinfunction "GNDA_8") (pintype "power_in"))
      (node (ref "NPC164") (pin "2") (pinfunction "GND_2") (pintype "power_in"))
      (node (ref "R1") (pin "1") (pinfunction "1_1") (pintype "passive"))
      (node (ref "R3") (pin "1") (pinfunction "1_1") (pintype "passive"))
      (node (ref "R6") (pin "1") (pinfunction "1_1") (pintype "passive"))
      (node (ref "U") (pin "14") (pinfunction "VSSA_14") (pintype "power_in"))
      (node (ref "U") (pin "16") (pinfunction "VSS_16") (pintype "power_in"))
      (node (ref "U") (pin "32") (pinfunction "VSS_32") (pintype "power_in"))
      (node (ref "U6") (pin "2") (pinfunction "VN_2") (pintype "power_in"))
    )
    (net (code "32") (name "GND PWR") (class "Default")
      (node (ref "Battery GND") (pin "1") (pintype "power_in"))
      (node (ref "C10") (pin "2") (pinfunction "2_2") (pintype "passive"))
      (node (ref "C11") (pin "2") (pinfunction "2_2") (pintype "passive"))
      (node (ref "C12") (pin "2") (pinfunction "2_2") (pintype "passive"))
      (node (ref "C13") (pin "2") (pinfunction "2_2") (pintype "passive"))
      (node (ref "C14") (pin "2") (pinfunction "2_2") (pintype "passive"))
      (node (ref "C16") (pin "2") (pinfunction "2_2") (pintype "passive"))
      (node (ref "C17") (pin "2") (pinfunction "2_2") (pintype "passive"))
      (node (ref "C22") (pin "2") (pinfunction "2_2") (pintype "passive"))
      (node (ref "C23") (pin "2") (pinfunction "2_2") (pintype "passive"))
      (node (ref "C3") (pin "2") (pinfunction "2_2") (pintype "passive"))
      (node (ref "C4") (pin "2") (pinfunction "2_2") (pintype "passive"))
      (node (ref "C5") (pin "2") (pinfunction "2_2") (pintype "passive"))
      (node (ref "C6") (pin "2") (pinfunction "2_2") (pintype "passive"))
      (node (ref "C7") (pin "2") (pinfunction "2_2") (pintype "passive"))
      (node (ref "C8") (pin "2") (pinfunction "2_2") (pintype "passive"))
      (node (ref "C9") (pin "2") (pinfunction "2_2") (pintype "passive"))
      (node (ref "D2") (pin "1") (pinfunction "C_1") (pintype "passive"))
      (node (ref "M1") (pin "10") (pinfunction "GNDB_10") (pintype "power_in"))
      (node (ref "M1") (pin "15") (pinfunction "ENB_15") (pintype "power_in"))
      (node (ref "M2") (pin "10") (pinfunction "GNDB_10") (pintype "power_in"))
      (node (ref "M2") (pin "15") (pinfunction "ENB_15") (pintype "power_in"))
      (node (ref "NVC8730") (pin "2") (pinfunction "GND_2") (pintype "power_in"))
      (node (ref "Q1") (pin "1") (pinfunction "G_1") (pintype "passive"))
      (node (ref "R10") (pin "2") (pinfunction "2_2") (pintype "passive"))
      (node (ref "R11") (pin "2") (pinfunction "2_2") (pintype "passive"))
      (node (ref "R12") (pin "2") (pinfunction "2_2") (pintype "passive"))
      (node (ref "R20") (pin "1") (pinfunction "1_1") (pintype "passive"))
      (node (ref "R21") (pin "1") (pinfunction "1_1") (pintype "passive"))
      (node (ref "R22") (pin "1") (pinfunction "1_1") (pintype "passive"))
      (node (ref "THROWER GND") (pin "1") (pintype "power_in"))
      (node (ref "U1") (pin "11") (pinfunction "DIAG_11") (pintype "input"))
      (node (ref "U1") (pin "14") (pinfunction "MODE_14") (pintype "input"))
      (node (ref "U1") (pin "6") (pinfunction "GND_6") (pintype "power_in"))
      (node (ref "U2") (pin "11") (pinfunction "DIAG_11") (pintype "input"))
      (node (ref "U2") (pin "14") (pinfunction "MODE_14") (pintype "input"))
      (node (ref "U2") (pin "6") (pinfunction "GND_6") (pintype "power_in"))
      (node (ref "U3") (pin "11") (pinfunction "DIAG_11") (pintype "input"))
      (node (ref "U3") (pin "14") (pinfunction "MODE_14") (pintype "input"))
      (node (ref "U3") (pin "6") (pinfunction "GND_6") (pintype "power_in"))
    )
    (net (code "33") (name "Net-(D1-A)") (class "Default")
      (node (ref "D1") (pin "2") (pinfunction "A_2") (pintype "passive"))
      (node (ref "R13") (pin "1") (pinfunction "1_1") (pintype "passive"))
    )
    (net (code "34") (name "Net-(D2-A)") (class "Default")
      (node (ref "D2") (pin "2") (pinfunction "A_2") (pintype "passive"))
      (node (ref "R8") (pin "2") (pinfunction "2_2") (pintype "passive"))
    )
    (net (code "35") (name "Net-(NPC164-EN)") (class "Default")
      (node (ref "NPC164") (pin "3") (pinfunction "EN_3") (pintype "power_in"))
      (node (ref "R7") (pin "2") (pinfunction "2_2") (pintype "passive"))
    )
    (net (code "36") (name "Net-(Q1-D)") (class "Default")
      (node (ref "Battery 16V") (pin "1") (pintype "power_in"))
      (node (ref "Q1") (pin "4") (pinfunction "D_4") (pintype "passive"))
    )
    (net (code "37") (name "Net-(U-PF0-OSC_IN)") (class "Default")
      (node (ref "R13") (pin "2") (pinfunction "2_2") (pintype "passive"))
      (node (ref "U") (pin "2") (pinfunction "PF0-OSC_IN_2") (pintype "bidirectional"))
    )
    (net (code "38") (name "Net-(U1-DRVOFF)") (class "Default")
      (node (ref "R6") (pin "2") (pinfunction "2_2") (pintype "passive"))
      (node (ref "U1") (pin "8") (pinfunction "DRVOFF_8") (pintype "input"))
    )
    (net (code "39") (name "Net-(U1-IPROPI)") (class "Default")
      (node (ref "R10") (pin "1") (pinfunction "1_1") (pintype "passive"))
      (node (ref "U1") (pin "2") (pinfunction "IPROPI_2") (pintype "bidirectional"))
    )
    (net (code "40") (name "Net-(U1-OUT1)") (class "Default")
      (node (ref "M1_OUT1") (pin "1") (pintype "power_in"))
      (node (ref "U1") (pin "7") (pinfunction "OUT1_7") (pintype "passive"))
    )
    (net (code "41") (name "Net-(U1-OUT2)") (class "Default")
      (node (ref "M1_OUT2") (pin "1") (pintype "power_in"))
      (node (ref "U1") (pin "5") (pinfunction "OUT2_5") (pintype "passive"))
    )
    (net (code "42") (name "Net-(U1-SR)") (class "Default")
      (node (ref "R20") (pin "2") (pinfunction "2_2") (pintype "passive"))
      (node (ref "U1") (pin "12") (pinfunction "SR_12") (pintype "input"))
    )
    (net (code "43") (name "Net-(U2-DRVOFF)") (class "Default")
      (node (ref "R3") (pin "2") (pinfunction "2_2") (pintype "passive"))
      (node (ref "U2") (pin "8") (pinfunction "DRVOFF_8") (pintype "input"))
    )
    (net (code "44") (name "Net-(U2-IPROPI)") (class "Default")
      (node (ref "R11") (pin "1") (pinfunction "1_1") (pintype "passive"))
      (node (ref "U2") (pin "2") (pinfunction "IPROPI_2") (pintype "bidirectional"))
    )
    (net (code "45") (name "Net-(U2-OUT1)") (class "Default")
      (node (ref "M2_OUT1") (pin "1") (pintype "power_in"))
      (node (ref "U2") (pin "7") (pinfunction "OUT1_7") (pintype "passive"))
    )
    (net (code "46") (name "Net-(U2-OUT2)") (class "Default")
      (node (ref "M2_OUT2") (pin "1") (pintype "power_in"))
      (node (ref "U2") (pin "5") (pinfunction "OUT2_5") (pintype "passive"))
    )
    (net (code "47") (name "Net-(U2-SR)") (class "Default")
      (node (ref "R21") (pin "2") (pinfunction "2_2") (pintype "passive"))
      (node (ref "U2") (pin "12") (pinfunction "SR_12") (pintype "input"))
    )
    (net (code "48") (name "Net-(U3-DRVOFF)") (class "Default")
      (node (ref "R1") (pin "2") (pinfunction "2_2") (pintype "passive"))
      (node (ref "U3") (pin "8") (pinfunction "DRVOFF_8") (pintype "input"))
    )
    (net (code "49") (name "Net-(U3-IPROPI)") (class "Default")
      (node (ref "R12") (pin "1") (pinfunction "1_1") (pintype "passive"))
      (node (ref "U3") (pin "2") (pinfunction "IPROPI_2") (pintype "bidirectional"))
    )
    (net (code "50") (name "Net-(U3-OUT1)") (class "Default")
      (node (ref "M3_OUT1") (pin "1") (pintype "power_in"))
      (node (ref "U3") (pin "7") (pinfunction "OUT1_7") (pintype "passive"))
    )
    (net (code "51") (name "Net-(U3-OUT2)") (class "Default")
      (node (ref "M3_OUT2") (pin "1") (pintype "power_in"))
      (node (ref "U3") (pin "5") (pinfunction "OUT2_5") (pintype "passive"))
    )
    (net (code "52") (name "Net-(U3-SR)") (class "Default")
      (node (ref "R22") (pin "2") (pinfunction "2_2") (pintype "passive"))
      (node (ref "U3") (pin "12") (pinfunction "SR_12") (pintype "input"))
    )
    (net (code "53") (name "unconnected-(J4-Pad3)") (class "Default")
      (node (ref "J4") (pin "3") (pinfunction "3_3") (pintype "passive"))
    )
    (net (code "54") (name "unconnected-(J4-Pad4)") (class "Default")
      (node (ref "J4") (pin "4") (pinfunction "4_4") (pintype "passive"))
    )
    (net (code "55") (name "unconnected-(J5-ID-Pad4)") (class "Default")
      (node (ref "J5") (pin "4") (pinfunction "ID_4") (pintype "passive"))
    )
    (net (code "56") (name "unconnected-(J6-Pad06)") (class "Default")
      (node (ref "J6") (pin "06") (pinfunction "06_06") (pintype "passive"))
    )
    (net (code "57") (name "unconnected-(J6-Pad07)") (class "Default")
      (node (ref "J6") (pin "07") (pinfunction "07_07") (pintype "passive"))
    )
    (net (code "58") (name "unconnected-(J6-Pad08)") (class "Default")
      (node (ref "J6") (pin "08") (pinfunction "08_08") (pintype "passive"))
    )
    (net (code "59") (name "unconnected-(M1-IC-Pad7)") (class "Default")
      (node (ref "M1") (pin "7") (pinfunction "IC_7") (pintype "passive"))
    )
    (net (code "60") (name "unconnected-(M1-VDDB-Pad9)") (class "Default")
      (node (ref "M1") (pin "9") (pinfunction "VDDB_9") (pintype "power_in"))
    )
    (net (code "61") (name "unconnected-(M2-IC-Pad7)") (class "Default")
      (node (ref "M2") (pin "7") (pinfunction "IC_7") (pintype "passive"))
    )
    (net (code "62") (name "unconnected-(M2-VDDB-Pad9)") (class "Default")
      (node (ref "M2") (pin "9") (pinfunction "VDDB_9") (pintype "power_in"))
    )
    (net (code "63") (name "unconnected-(NPC164-PG{slash}ADJ-Pad5)") (class "Default")
      (node (ref "NPC164") (pin "5") (pinfunction "PG/ADJ_5") (pintype "passive"))
    )
    (net (code "64") (name "unconnected-(NVC8730-EN-Pad3)") (class "Default")
      (node (ref "NVC8730") (pin "3") (pinfunction "EN_3") (pintype "power_in"))
    )
    (net (code "65") (name "unconnected-(NVC8730-OUT-Pad4)") (class "Default")
      (node (ref "NVC8730") (pin "4") (pinfunction "OUT_4") (pintype "power_in"))
    )
    (net (code "66") (name "unconnected-(U-PA10-Pad20)") (class "Default")
      (node (ref "U") (pin "20") (pinfunction "PA10_20") (pintype "bidirectional"))
    )
    (net (code "67") (name "unconnected-(U-PA15-Pad25)") (class "Default")
      (node (ref "U") (pin "25") (pinfunction "PA15_25") (pintype "bidirectional"))
    )
    (net (code "68") (name "unconnected-(U-PB0-Pad13)") (class "Default")
      (node (ref "U") (pin "13") (pinfunction "PB0_13") (pintype "bidirectional"))
    )
    (net (code "69") (name "unconnected-(U-PB3-Pad26)") (class "Default")
      (node (ref "U") (pin "26") (pinfunction "PB3_26") (pintype "bidirectional"))
    )
    (net (code "70") (name "unconnected-(U-PB8-BOOT0-Pad31)") (class "Default")
      (node (ref "U") (pin "31") (pinfunction "PB8-BOOT0_31") (pintype "bidirectional"))
    )
    (net (code "71") (name "unconnected-(U-PF1-OSC_OUT-Pad3)") (class "Default")
      (node (ref "U") (pin "3") (pinfunction "PF1-OSC_OUT_3") (pintype "bidirectional"))
    )
    (net (code "72") (name "unconnected-(U1-ITRIP-Pad13)") (class "Default")
      (node (ref "U1") (pin "13") (pinfunction "ITRIP_13") (pintype "input+no_connect"))
    )
    (net (code "73") (name "unconnected-(U1-~{FAULT}-Pad1)") (class "Default")
      (node (ref "U1") (pin "1") (pinfunction "~{FAULT}_1") (pintype "output"))
    )
    (net (code "74") (name "unconnected-(U2-ITRIP-Pad13)") (class "Default")
      (node (ref "U2") (pin "13") (pinfunction "ITRIP_13") (pintype "input+no_connect"))
    )
    (net (code "75") (name "unconnected-(U2-~{FAULT}-Pad1)") (class "Default")
      (node (ref "U2") (pin "1") (pinfunction "~{FAULT}_1") (pintype "output"))
    )
    (net (code "76") (name "unconnected-(U3-ITRIP-Pad13)") (class "Default")
      (node (ref "U3") (pin "13") (pinfunction "ITRIP_13") (pintype "input+no_connect"))
    )
    (net (code "77") (name "unconnected-(U3-~{FAULT}-Pad1)") (class "Default")
      (node (ref "U3") (pin "1") (pinfunction "~{FAULT}_1") (pintype "output"))
    )
    (net (code "78") (name "unconnected-(U6-NC-Pad1)") (class "Default")
      (node (ref "U6") (pin "1") (pinfunction "NC_1") (pintype "passive"))
    )
  )
)
